# 519_jetson_nano_107.net
KiCad netlist of a schematic drawn in EAGLE
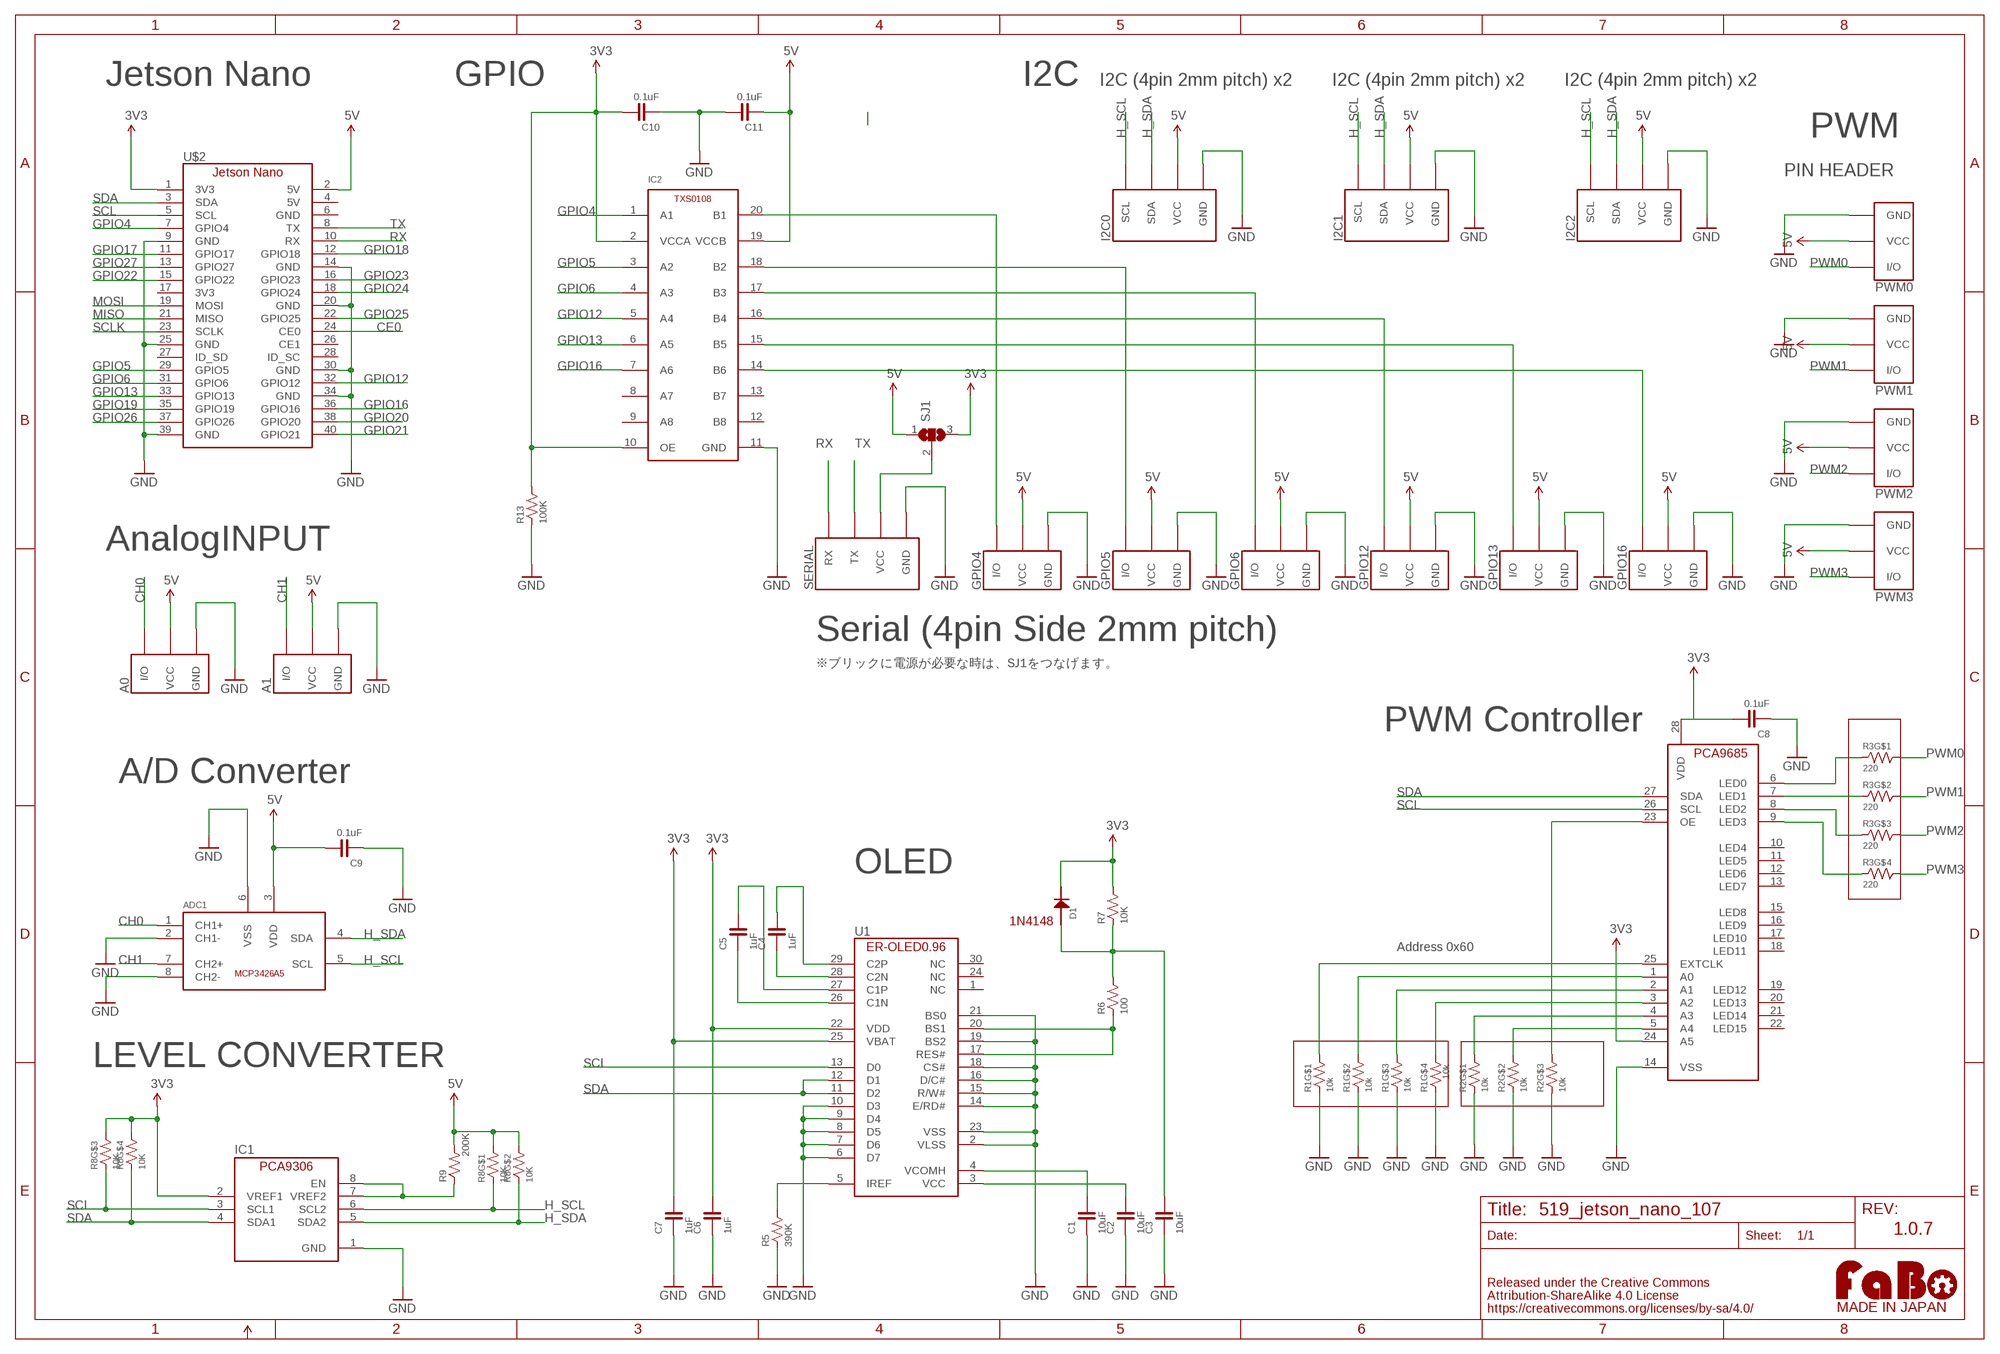
[diagram p0: schematic, sheet 1]

(export (version "E")
  (design (tool "Eeschema 10.0.6"))
  (components
    (comp (ref "A0")
      (value "FABO_BRICK_3PIN-S03B-PASK-2")
      (footprint "eagle-import:FABO_BRICK_3PIN_S03B-PASK-2")
      (libsource (lib "eagle-import") (part "FABO_BRICK_3PIN-S03B-PASK-2"))
    )
    (comp (ref "A1")
      (value "FABO_BRICK_3PIN-S03B-PASK-2")
      (footprint "eagle-import:FABO_BRICK_3PIN_S03B-PASK-2")
      (libsource (lib "eagle-import") (part "FABO_BRICK_3PIN-S03B-PASK-2"))
    )
    (comp (ref "ADC1")
      (value "MICROCHIP-MCP3426")
      (footprint "eagle-import:MICROCHIP-MCP3426")
      (libsource (lib "eagle-import") (part "MICROCHIP-MCP3426"))
    )
    (comp (ref "C1")
      (value "10uF")
      (footprint "eagle-import:0603-BOTTOM")
      (libsource (lib "eagle-import") (part "CAPACITOR-0603-BOTTOM"))
    )
    (comp (ref "C2")
      (value "10uF")
      (footprint "eagle-import:0603-BOTTOM")
      (libsource (lib "eagle-import") (part "CAPACITOR-0603-BOTTOM"))
    )
    (comp (ref "C3")
      (value "10uF")
      (footprint "eagle-import:0603-BOTTOM")
      (libsource (lib "eagle-import") (part "CAPACITOR-0603-BOTTOM"))
    )
    (comp (ref "C4")
      (value "1uF")
      (footprint "eagle-import:0603-BOTTOM")
      (libsource (lib "eagle-import") (part "CAPACITOR-0603-BOTTOM"))
    )
    (comp (ref "C5")
      (value "1uF")
      (footprint "eagle-import:0603-BOTTOM")
      (libsource (lib "eagle-import") (part "CAPACITOR-0603-BOTTOM"))
    )
    (comp (ref "C6")
      (value "1uF")
      (footprint "eagle-import:0603-BOTTOM")
      (libsource (lib "eagle-import") (part "CAPACITOR-0603-BOTTOM"))
    )
    (comp (ref "C7")
      (value "1uF")
      (footprint "eagle-import:0603-BOTTOM")
      (libsource (lib "eagle-import") (part "CAPACITOR-0603-BOTTOM"))
    )
    (comp (ref "C8")
      (value "0.1uF")
      (footprint "eagle-import:0603")
      (libsource (lib "eagle-import") (part "CAPACITOR-0603"))
    )
    (comp (ref "C9")
      (value "0.1uF")
      (footprint "eagle-import:0603")
      (libsource (lib "eagle-import") (part "CAPACITOR-0603"))
    )
    (comp (ref "C10")
      (value "0.1uF")
      (footprint "eagle-import:0603")
      (libsource (lib "eagle-import") (part "CAPACITOR-0603"))
    )
    (comp (ref "C11")
      (value "0.1uF")
      (footprint "eagle-import:0603")
      (libsource (lib "eagle-import") (part "CAPACITOR-0603"))
    )
    (comp (ref "D1")
      (value "1N4148")
      (footprint "eagle-import:1N4148W")
      (libsource (lib "eagle-import") (part "1N4148"))
    )
    (comp (ref "GPIO4")
      (value "FABO_BRICK_3PIN-B03B-PASK-1")
      (footprint "eagle-import:FABO_BRICK_3PIN_B03B-PASK-1")
      (libsource (lib "eagle-import") (part "FABO_BRICK_3PIN-B03B-PASK-1"))
    )
    (comp (ref "GPIO5")
      (value "FABO_BRICK_3PIN-B03B-PASK-1")
      (footprint "eagle-import:FABO_BRICK_3PIN_B03B-PASK-1")
      (libsource (lib "eagle-import") (part "FABO_BRICK_3PIN-B03B-PASK-1"))
    )
    (comp (ref "GPIO6")
      (value "FABO_BRICK_3PIN-B03B-PASK-1")
      (footprint "eagle-import:FABO_BRICK_3PIN_B03B-PASK-1")
      (libsource (lib "eagle-import") (part "FABO_BRICK_3PIN-B03B-PASK-1"))
    )
    (comp (ref "GPIO12")
      (value "FABO_BRICK_3PIN-B03B-PASK-1")
      (footprint "eagle-import:FABO_BRICK_3PIN_B03B-PASK-1")
      (libsource (lib "eagle-import") (part "FABO_BRICK_3PIN-B03B-PASK-1"))
    )
    (comp (ref "GPIO13")
      (value "FABO_BRICK_3PIN-B03B-PASK-1")
      (footprint "eagle-import:FABO_BRICK_3PIN_B03B-PASK-1")
      (libsource (lib "eagle-import") (part "FABO_BRICK_3PIN-B03B-PASK-1"))
    )
    (comp (ref "GPIO16")
      (value "FABO_BRICK_3PIN-B03B-PASK-1")
      (footprint "eagle-import:FABO_BRICK_3PIN_B03B-PASK-1")
      (libsource (lib "eagle-import") (part "FABO_BRICK_3PIN-B03B-PASK-1"))
    )
    (comp (ref "I2C0")
      (value "FABO_BRICK_I2C-S04B-PASK-2")
      (footprint "eagle-import:FABO_BRICK_I2C_S04B-PASK-2")
      (libsource (lib "eagle-import") (part "FABO_BRICK_I2C-S04B-PASK-2"))
    )
    (comp (ref "I2C1")
      (value "FABO_BRICK_I2C-B04B-PASK-1")
      (footprint "eagle-import:FABO_BRICK_I2C_B04B-PASK-1")
      (libsource (lib "eagle-import") (part "FABO_BRICK_I2C-B04B-PASK-1"))
    )
    (comp (ref "I2C2")
      (value "FABO_BRICK_I2C-B04B-PASK-1")
      (footprint "eagle-import:FABO_BRICK_I2C_B04B-PASK-1")
      (libsource (lib "eagle-import") (part "FABO_BRICK_I2C-B04B-PASK-1"))
    )
    (comp (ref "IC1")
      (value "PCA9306_SSOP")
      (footprint "eagle-import:8PIN-SSOP")
      (libsource (lib "eagle-import") (part "PCA9306_SSOP"))
    )
    (comp (ref "IC2")
      (value "TXS0108")
      (footprint "eagle-import:R-PUSON-N20")
      (libsource (lib "eagle-import") (part "TXS0108"))
    )
    (comp (ref "PWM0")
      (value "FABO_BRICK_3PIN-HEADER")
      (footprint "eagle-import:FABO_BRICK_3PIN_HEADER")
      (libsource (lib "eagle-import") (part "FABO_BRICK_3PIN-HEADER"))
    )
    (comp (ref "PWM1")
      (value "FABO_BRICK_3PIN-HEADER")
      (footprint "eagle-import:FABO_BRICK_3PIN_HEADER")
      (libsource (lib "eagle-import") (part "FABO_BRICK_3PIN-HEADER"))
    )
    (comp (ref "PWM2")
      (value "FABO_BRICK_3PIN-HEADER")
      (footprint "eagle-import:FABO_BRICK_3PIN_HEADER")
      (libsource (lib "eagle-import") (part "FABO_BRICK_3PIN-HEADER"))
    )
    (comp (ref "PWM3")
      (value "FABO_BRICK_3PIN-HEADER")
      (footprint "eagle-import:FABO_BRICK_3PIN_HEADER")
      (libsource (lib "eagle-import") (part "FABO_BRICK_3PIN-HEADER"))
    )
    (comp (ref "R1")
      (value "10k")
      (footprint "eagle-import:EXBV8V")
      (libsource (lib "eagle-import") (part "RESISTOR_ARRAY"))
    )
    (comp (ref "R2")
      (value "10k")
      (footprint "eagle-import:EXBV8V")
      (libsource (lib "eagle-import") (part "RESISTOR_ARRAY"))
    )
    (comp (ref "R3")
      (value "220")
      (footprint "eagle-import:EXBV8V")
      (libsource (lib "eagle-import") (part "RESISTOR_ARRAY"))
    )
    (comp (ref "R5")
      (value "390K")
      (footprint "eagle-import:0603-BOTTOM")
      (libsource (lib "eagle-import") (part "RESISTOR-0603-BOTTOM"))
    )
    (comp (ref "R6")
      (value "100")
      (footprint "eagle-import:0603-BOTTOM")
      (libsource (lib "eagle-import") (part "RESISTOR-0603-BOTTOM"))
    )
    (comp (ref "R7")
      (value "10K")
      (footprint "eagle-import:0603-BOTTOM")
      (libsource (lib "eagle-import") (part "RESISTOR-0603-BOTTOM"))
    )
    (comp (ref "R8")
      (value "10K")
      (footprint "eagle-import:EXBV8V")
      (libsource (lib "eagle-import") (part "RESISTOR_ARRAY"))
    )
    (comp (ref "R9")
      (value "200K")
      (footprint "eagle-import:0603")
      (libsource (lib "eagle-import") (part "RESISTOR-0603"))
    )
    (comp (ref "R13")
      (value "100K")
      (footprint "eagle-import:0603-BOTTOM")
      (libsource (lib "eagle-import") (part "RESISTOR-0603-BOTTOM"))
    )
    (comp (ref "SERIAL")
      (value "FABO_BRICK_SERIAL-B04B-PASK-1")
      (footprint "eagle-import:FABO_BRICK_SERIAL_B04B-PASK-1")
      (libsource (lib "eagle-import") (part "FABO_BRICK_SERIAL-B04B-PASK-1"))
    )
    (comp (ref "SJ1")
      (value "SJ2W")
      (footprint "eagle-import:SJ_2")
      (libsource (lib "eagle-import") (part "SJ2W"))
    )
    (comp (ref "U$2")
      (value "JETSON_NANO_WIDE")
      (footprint "eagle-import:JETSON_NANO_WIDE")
      (libsource (lib "eagle-import") (part "JETSON_NANO_WIDE"))
    )
    (comp (ref "U$9")
      (value "PCA9685")
      (footprint "eagle-import:PCA9685")
      (libsource (lib "eagle-import") (part "PCA9685"))
    )
    (comp (ref "U$14")
      (value "LOGO_FABO-M")
      (footprint "eagle-import:LOGO_FABO_MS")
      (libsource (lib "eagle-import") (part "LOGO_FABO-M"))
    )
    (comp (ref "U1")
      (value "ER-OLED0.96-1ER-CON30HT-1")
      (footprint "eagle-import:ER-CON30HT-1")
      (libsource (lib "eagle-import") (part "ER-OLED0.96-1ER-CON30HT-1"))
    )
  )
  (nets
    (net (code "1") (name "/CE0") (class "Default")
      (node (ref "U$2") (pin "24") (pinfunction "CE0_24") (pintype "bidirectional"))
    )
    (net (code "2") (name "/CH0") (class "Default")
      (node (ref "A0") (pin "I/O") (pinfunction "I/O_I/O") (pintype "bidirectional"))
      (node (ref "ADC1") (pin "1") (pinfunction "CH1+_1") (pintype "bidirectional"))
    )
    (net (code "3") (name "/CH1") (class "Default")
      (node (ref "A1") (pin "I/O") (pinfunction "I/O_I/O") (pintype "bidirectional"))
      (node (ref "ADC1") (pin "7") (pinfunction "CH2+_7") (pintype "bidirectional"))
    )
    (net (code "4") (name "/GPIO4") (class "Default")
      (node (ref "IC2") (pin "1") (pinfunction "A1_1") (pintype "bidirectional"))
      (node (ref "U$2") (pin "7") (pinfunction "GPIO4_7") (pintype "bidirectional"))
    )
    (net (code "5") (name "/GPIO5") (class "Default")
      (node (ref "IC2") (pin "3") (pinfunction "A2_3") (pintype "bidirectional"))
      (node (ref "U$2") (pin "29") (pinfunction "GPIO5_29") (pintype "bidirectional"))
    )
    (net (code "6") (name "/GPIO6") (class "Default")
      (node (ref "IC2") (pin "4") (pinfunction "A3_4") (pintype "bidirectional"))
      (node (ref "U$2") (pin "31") (pinfunction "GPIO6_31") (pintype "bidirectional"))
    )
    (net (code "7") (name "/GPIO12") (class "Default")
      (node (ref "IC2") (pin "5") (pinfunction "A4_5") (pintype "bidirectional"))
      (node (ref "U$2") (pin "32") (pinfunction "GPIO12_32") (pintype "bidirectional"))
    )
    (net (code "8") (name "/GPIO13") (class "Default")
      (node (ref "IC2") (pin "6") (pinfunction "A5_6") (pintype "bidirectional"))
      (node (ref "U$2") (pin "33") (pinfunction "GPIO13_33") (pintype "bidirectional"))
    )
    (net (code "9") (name "/GPIO16") (class "Default")
      (node (ref "IC2") (pin "7") (pinfunction "A6_7") (pintype "bidirectional"))
      (node (ref "U$2") (pin "36") (pinfunction "GPIO16_36") (pintype "bidirectional"))
    )
    (net (code "10") (name "/GPIO17") (class "Default")
      (node (ref "U$2") (pin "11") (pinfunction "GPIO17_11") (pintype "bidirectional"))
    )
    (net (code "11") (name "/GPIO18") (class "Default")
      (node (ref "U$2") (pin "12") (pinfunction "GPIO18_12") (pintype "bidirectional"))
    )
    (net (code "12") (name "/GPIO19") (class "Default")
      (node (ref "U$2") (pin "35") (pinfunction "GPIO19_35") (pintype "bidirectional"))
    )
    (net (code "13") (name "/GPIO20") (class "Default")
      (node (ref "U$2") (pin "38") (pinfunction "GPIO20_38") (pintype "bidirectional"))
    )
    (net (code "14") (name "/GPIO21") (class "Default")
      (node (ref "U$2") (pin "40") (pinfunction "GPIO21_40") (pintype "bidirectional"))
    )
    (net (code "15") (name "/GPIO22") (class "Default")
      (node (ref "U$2") (pin "15") (pinfunction "GPIO22_15") (pintype "bidirectional"))
    )
    (net (code "16") (name "/GPIO23") (class "Default")
      (node (ref "U$2") (pin "16") (pinfunction "GPIO23_16") (pintype "bidirectional"))
    )
    (net (code "17") (name "/GPIO24") (class "Default")
      (node (ref "U$2") (pin "18") (pinfunction "GPIO24_18") (pintype "bidirectional"))
    )
    (net (code "18") (name "/GPIO25") (class "Default")
      (node (ref "U$2") (pin "22") (pinfunction "GPIO25_22") (pintype "bidirectional"))
    )
    (net (code "19") (name "/GPIO26") (class "Default")
      (node (ref "U$2") (pin "37") (pinfunction "GPIO26_37") (pintype "bidirectional"))
    )
    (net (code "20") (name "/GPIO27") (class "Default")
      (node (ref "U$2") (pin "13") (pinfunction "GPIO27_13") (pintype "bidirectional"))
    )
    (net (code "21") (name "/H_SCL") (class "Default")
      (node (ref "ADC1") (pin "5") (pinfunction "SCL_5") (pintype "bidirectional"))
      (node (ref "I2C0") (pin "SCL") (pinfunction "SCL_SCL") (pintype "bidirectional"))
      (node (ref "I2C1") (pin "SCL") (pinfunction "SCL_SCL") (pintype "bidirectional"))
      (node (ref "I2C2") (pin "SCL") (pinfunction "SCL_SCL") (pintype "bidirectional"))
      (node (ref "IC1") (pin "6") (pinfunction "SCL2_6") (pintype "bidirectional"))
      (node (ref "R8") (pin "1") (pinfunction "1_1") (pintype "bidirectional"))
    )
    (net (code "22") (name "/H_SDA") (class "Default")
      (node (ref "ADC1") (pin "4") (pinfunction "SDA_4") (pintype "bidirectional"))
      (node (ref "I2C0") (pin "SDA") (pinfunction "SDA_SDA") (pintype "bidirectional"))
      (node (ref "I2C1") (pin "SDA") (pinfunction "SDA_SDA") (pintype "bidirectional"))
      (node (ref "I2C2") (pin "SDA") (pinfunction "SDA_SDA") (pintype "bidirectional"))
      (node (ref "IC1") (pin "5") (pinfunction "SDA2_5") (pintype "bidirectional"))
      (node (ref "R8") (pin "2") (pinfunction "1_2") (pintype "bidirectional"))
    )
    (net (code "23") (name "/MISO") (class "Default")
      (node (ref "U$2") (pin "21") (pinfunction "MISO_21") (pintype "bidirectional"))
    )
    (net (code "24") (name "/MOSI") (class "Default")
      (node (ref "U$2") (pin "19") (pinfunction "MOSI_19") (pintype "bidirectional"))
    )
    (net (code "25") (name "/PWM0") (class "Default")
      (node (ref "PWM0") (pin "I/O") (pinfunction "I/O_I/O") (pintype "bidirectional"))
      (node (ref "R3") (pin "8") (pinfunction "2_8") (pintype "bidirectional"))
    )
    (net (code "26") (name "/PWM1") (class "Default")
      (node (ref "PWM1") (pin "I/O") (pinfunction "I/O_I/O") (pintype "bidirectional"))
      (node (ref "R3") (pin "7") (pinfunction "2_7") (pintype "bidirectional"))
    )
    (net (code "27") (name "/PWM2") (class "Default")
      (node (ref "PWM2") (pin "I/O") (pinfunction "I/O_I/O") (pintype "bidirectional"))
      (node (ref "R3") (pin "6") (pinfunction "2_6") (pintype "bidirectional"))
    )
    (net (code "28") (name "/PWM3") (class "Default")
      (node (ref "PWM3") (pin "I/O") (pinfunction "I/O_I/O") (pintype "bidirectional"))
      (node (ref "R3") (pin "5") (pinfunction "2_5") (pintype "bidirectional"))
    )
    (net (code "29") (name "/RX") (class "Default")
      (node (ref "SERIAL") (pin "RX") (pinfunction "RX_RX") (pintype "bidirectional"))
      (node (ref "U$2") (pin "10") (pinfunction "RX_10") (pintype "bidirectional"))
    )
    (net (code "30") (name "/SCL") (class "Default")
      (node (ref "IC1") (pin "3") (pinfunction "SCL1_3") (pintype "bidirectional"))
      (node (ref "R8") (pin "3") (pinfunction "1_3") (pintype "bidirectional"))
      (node (ref "U$2") (pin "5") (pinfunction "SCL_5") (pintype "bidirectional"))
      (node (ref "U$9") (pin "26") (pinfunction "SCL_26") (pintype "bidirectional"))
      (node (ref "U1") (pin "13") (pinfunction "D0_13") (pintype "bidirectional"))
    )
    (net (code "31") (name "/SCLK") (class "Default")
      (node (ref "U$2") (pin "23") (pinfunction "SCLK_23") (pintype "bidirectional"))
    )
    (net (code "32") (name "/SDA") (class "Default")
      (node (ref "IC1") (pin "4") (pinfunction "SDA1_4") (pintype "bidirectional"))
      (node (ref "R8") (pin "4") (pinfunction "1_4") (pintype "bidirectional"))
      (node (ref "U$2") (pin "3") (pinfunction "SDA_3") (pintype "bidirectional"))
      (node (ref "U$9") (pin "27") (pinfunction "SDA_27") (pintype "bidirectional"))
      (node (ref "U1") (pin "11") (pinfunction "D2_11") (pintype "bidirectional"))
      (node (ref "U1") (pin "12") (pinfunction "D1_12") (pintype "bidirectional"))
    )
    (net (code "33") (name "/TX") (class "Default")
      (node (ref "SERIAL") (pin "TX") (pinfunction "TX_TX") (pintype "bidirectional"))
      (node (ref "U$2") (pin "8") (pinfunction "TX_8") (pintype "bidirectional"))
    )
    (net (code "34") (name "3V3") (class "Default")
      (node (ref "C10") (pin "2") (pinfunction "2_2") (pintype "passive"))
      (node (ref "C6") (pin "2") (pinfunction "2_2") (pintype "passive"))
      (node (ref "C7") (pin "2") (pinfunction "2_2") (pintype "passive"))
      (node (ref "C8") (pin "2") (pinfunction "2_2") (pintype "passive"))
      (node (ref "D1") (pin "CATHODE") (pinfunction "CATHODE_CATHODE") (pintype "bidirectional"))
      (node (ref "IC1") (pin "2") (pinfunction "VREF1_2") (pintype "bidirectional"))
      (node (ref "IC2") (pin "10") (pinfunction "OE_10") (pintype "bidirectional"))
      (node (ref "IC2") (pin "2") (pinfunction "VCCA_2") (pintype "bidirectional"))
      (node (ref "R13") (pin "2") (pinfunction "2_2") (pintype "bidirectional"))
      (node (ref "R7") (pin "2") (pinfunction "2_2") (pintype "bidirectional"))
      (node (ref "R8") (pin "5") (pinfunction "2_5") (pintype "bidirectional"))
      (node (ref "R8") (pin "6") (pinfunction "2_6") (pintype "bidirectional"))
      (node (ref "SJ1") (pin "3") (pinfunction "3_3") (pintype "passive"))
      (node (ref "U$2") (pin "1") (pinfunction "3V3_1") (pintype "bidirectional"))
      (node (ref "U$9") (pin "24") (pinfunction "A5_24") (pintype "bidirectional"))
      (node (ref "U$9") (pin "28") (pinfunction "VDD_28") (pintype "bidirectional"))
      (node (ref "U1") (pin "22") (pinfunction "VDD_22") (pintype "bidirectional"))
      (node (ref "U1") (pin "25") (pinfunction "VBAT_25") (pintype "bidirectional"))
    )
    (net (code "35") (name "5V") (class "Default")
      (node (ref "A0") (pin "VCC") (pinfunction "VCC_VCC") (pintype "bidirectional"))
      (node (ref "A1") (pin "VCC") (pinfunction "VCC_VCC") (pintype "bidirectional"))
      (node (ref "ADC1") (pin "3") (pinfunction "VDD_3") (pintype "bidirectional"))
      (node (ref "C11") (pin "1") (pinfunction "1_1") (pintype "passive"))
      (node (ref "C9") (pin "2") (pinfunction "2_2") (pintype "passive"))
      (node (ref "GPIO12") (pin "VCC") (pinfunction "VCC_VCC") (pintype "bidirectional"))
      (node (ref "GPIO13") (pin "VCC") (pinfunction "VCC_VCC") (pintype "bidirectional"))
      (node (ref "GPIO16") (pin "VCC") (pinfunction "VCC_VCC") (pintype "bidirectional"))
      (node (ref "GPIO4") (pin "VCC") (pinfunction "VCC_VCC") (pintype "bidirectional"))
      (node (ref "GPIO5") (pin "VCC") (pinfunction "VCC_VCC") (pintype "bidirectional"))
      (node (ref "GPIO6") (pin "VCC") (pinfunction "VCC_VCC") (pintype "bidirectional"))
      (node (ref "I2C0") (pin "VCC") (pinfunction "VCC_VCC") (pintype "bidirectional"))
      (node (ref "I2C1") (pin "VCC") (pinfunction "VCC_VCC") (pintype "bidirectional"))
      (node (ref "I2C2") (pin "VCC") (pinfunction "VCC_VCC") (pintype "bidirectional"))
      (node (ref "IC2") (pin "19") (pinfunction "VCCB_19") (pintype "bidirectional"))
      (node (ref "PWM0") (pin "VCC") (pinfunction "VCC_VCC") (pintype "bidirectional"))
      (node (ref "PWM1") (pin "VCC") (pinfunction "VCC_VCC") (pintype "bidirectional"))
      (node (ref "PWM2") (pin "VCC") (pinfunction "VCC_VCC") (pintype "bidirectional"))
      (node (ref "PWM3") (pin "VCC") (pinfunction "VCC_VCC") (pintype "bidirectional"))
      (node (ref "R8") (pin "7") (pinfunction "2_7") (pintype "bidirectional"))
      (node (ref "R8") (pin "8") (pinfunction "2_8") (pintype "bidirectional"))
      (node (ref "R9") (pin "2") (pinfunction "2_2") (pintype "bidirectional"))
      (node (ref "SJ1") (pin "1") (pinfunction "1_1") (pintype "passive"))
      (node (ref "U$2") (pin "2") (pinfunction "5V_2") (pintype "bidirectional"))
    )
    (net (code "36") (name "GND") (class "Default")
      (node (ref "A0") (pin "GND") (pinfunction "GND_GND") (pintype "bidirectional"))
      (node (ref "A1") (pin "GND") (pinfunction "GND_GND") (pintype "bidirectional"))
      (node (ref "ADC1") (pin "2") (pinfunction "CH1-_2") (pintype "bidirectional"))
      (node (ref "ADC1") (pin "6") (pinfunction "VSS_6") (pintype "bidirectional"))
      (node (ref "ADC1") (pin "8") (pinfunction "CH2-_8") (pintype "bidirectional"))
      (node (ref "C1") (pin "1") (pinfunction "1_1") (pintype "passive"))
      (node (ref "C10") (pin "1") (pinfunction "1_1") (pintype "passive"))
      (node (ref "C11") (pin "2") (pinfunction "2_2") (pintype "passive"))
      (node (ref "C2") (pin "1") (pinfunction "1_1") (pintype "passive"))
      (node (ref "C3") (pin "1") (pinfunction "1_1") (pintype "passive"))
      (node (ref "C6") (pin "1") (pinfunction "1_1") (pintype "passive"))
      (node (ref "C7") (pin "1") (pinfunction "1_1") (pintype "passive"))
      (node (ref "C8") (pin "1") (pinfunction "1_1") (pintype "passive"))
      (node (ref "C9") (pin "1") (pinfunction "1_1") (pintype "passive"))
      (node (ref "GPIO12") (pin "GND") (pinfunction "GND_GND") (pintype "bidirectional"))
      (node (ref "GPIO13") (pin "GND") (pinfunction "GND_GND") (pintype "bidirectional"))
      (node (ref "GPIO16") (pin "GND") (pinfunction "GND_GND") (pintype "bidirectional"))
      (node (ref "GPIO4") (pin "GND") (pinfunction "GND_GND") (pintype "bidirectional"))
      (node (ref "GPIO5") (pin "GND") (pinfunction "GND_GND") (pintype "bidirectional"))
      (node (ref "GPIO6") (pin "GND") (pinfunction "GND_GND") (pintype "bidirectional"))
      (node (ref "I2C0") (pin "GND") (pinfunction "GND_GND") (pintype "bidirectional"))
      (node (ref "I2C1") (pin "GND") (pinfunction "GND_GND") (pintype "bidirectional"))
      (node (ref "I2C2") (pin "GND") (pinfunction "GND_GND") (pintype "bidirectional"))
      (node (ref "IC1") (pin "1") (pinfunction "GND_1") (pintype "bidirectional"))
      (node (ref "IC2") (pin "11") (pinfunction "GND_11") (pintype "bidirectional"))
      (node (ref "PWM0") (pin "GND") (pinfunction "GND_GND") (pintype "bidirectional"))
      (node (ref "PWM1") (pin "GND") (pinfunction "GND_GND") (pintype "bidirectional"))
      (node (ref "PWM2") (pin "GND") (pinfunction "GND_GND") (pintype "bidirectional"))
      (node (ref "PWM3") (pin "GND") (pinfunction "GND_GND") (pintype "bidirectional"))
      (node (ref "R1") (pin "1") (pinfunction "1_1") (pintype "bidirectional"))
      (node (ref "R1") (pin "2") (pinfunction "1_2") (pintype "bidirectional"))
      (node (ref "R1") (pin "3") (pinfunction "1_3") (pintype "bidirectional"))
      (node (ref "R1") (pin "4") (pinfunction "1_4") (pintype "bidirectional"))
      (node (ref "R13") (pin "1") (pinfunction "1_1") (pintype "bidirectional"))
      (node (ref "R2") (pin "1") (pinfunction "1_1") (pintype "bidirectional"))
      (node (ref "R2") (pin "2") (pinfunction "1_2") (pintype "bidirectional"))
      (node (ref "R2") (pin "3") (pinfunction "1_3") (pintype "bidirectional"))
      (node (ref "R5") (pin "1") (pinfunction "1_1") (pintype "bidirectional"))
      (node (ref "SERIAL") (pin "GND") (pinfunction "GND_GND") (pintype "bidirectional"))
      (node (ref "U$2") (pin "14") (pinfunction "GND_14") (pintype "bidirectional"))
      (node (ref "U$2") (pin "20") (pinfunction "GND_20") (pintype "bidirectional"))
      (node (ref "U$2") (pin "25") (pinfunction "GND_25") (pintype "bidirectional"))
      (node (ref "U$2") (pin "30") (pinfunction "GND_30") (pintype "bidirectional"))
      (node (ref "U$2") (pin "34") (pinfunction "GND_34") (pintype "bidirectional"))
      (node (ref "U$2") (pin "39") (pinfunction "GND_39") (pintype "bidirectional"))
      (node (ref "U$2") (pin "9") (pinfunction "GND_9") (pintype "bidirectional"))
      (node (ref "U$9") (pin "14") (pinfunction "VSS_14") (pintype "bidirectional"))
      (node (ref "U1") (pin "10") (pinfunction "D3_10") (pintype "bidirectional"))
      (node (ref "U1") (pin "14") (pinfunction "E/RD#_14") (pintype "bidirectional"))
      (node (ref "U1") (pin "15") (pinfunction "R/W#_15") (pintype "bidirectional"))
      (node (ref "U1") (pin "16") (pinfunction "D/C#_16") (pintype "bidirectional"))
      (node (ref "U1") (pin "18") (pinfunction "CS#_18") (pintype "bidirectional"))
      (node (ref "U1") (pin "19") (pinfunction "BS2_19") (pintype "bidirectional"))
      (node (ref "U1") (pin "2") (pinfunction "VLSS_2") (pintype "bidirectional"))
      (node (ref "U1") (pin "21") (pinfunction "BS0_21") (pintype "bidirectional"))
      (node (ref "U1") (pin "23") (pinfunction "VSS_23") (pintype "bidirectional"))
      (node (ref "U1") (pin "6") (pinfunction "D7_6") (pintype "bidirectional"))
      (node (ref "U1") (pin "7") (pinfunction "D6_7") (pintype "bidirectional"))
      (node (ref "U1") (pin "8") (pinfunction "D5_8") (pintype "bidirectional"))
      (node (ref "U1") (pin "9") (pinfunction "D4_9") (pintype "bidirectional"))
    )
    (net (code "37") (name "Net-(C3-Pad2)") (class "Default")
      (node (ref "C3") (pin "2") (pinfunction "2_2") (pintype "passive"))
      (node (ref "D1") (pin "ANODE") (pinfunction "ANODE_ANODE") (pintype "bidirectional"))
      (node (ref "R6") (pin "2") (pinfunction "2_2") (pintype "bidirectional"))
      (node (ref "R7") (pin "1") (pinfunction "1_1") (pintype "bidirectional"))
    )
    (net (code "38") (name "Net-(IC1-EN)") (class "Default")
      (node (ref "IC1") (pin "7") (pinfunction "VREF2_7") (pintype "bidirectional"))
      (node (ref "IC1") (pin "8") (pinfunction "EN_8") (pintype "bidirectional"))
      (node (ref "R9") (pin "1") (pinfunction "1_1") (pintype "bidirectional"))
    )
    (net (code "39") (name "Net-(IC2-B1)") (class "Default")
      (node (ref "GPIO4") (pin "I/O") (pinfunction "I/O_I/O") (pintype "bidirectional"))
      (node (ref "IC2") (pin "20") (pinfunction "B1_20") (pintype "bidirectional"))
    )
    (net (code "40") (name "Net-(IC2-B2)") (class "Default")
      (node (ref "GPIO5") (pin "I/O") (pinfunction "I/O_I/O") (pintype "bidirectional"))
      (node (ref "IC2") (pin "18") (pinfunction "B2_18") (pintype "bidirectional"))
    )
    (net (code "41") (name "Net-(IC2-B3)") (class "Default")
      (node (ref "GPIO6") (pin "I/O") (pinfunction "I/O_I/O") (pintype "bidirectional"))
      (node (ref "IC2") (pin "17") (pinfunction "B3_17") (pintype "bidirectional"))
    )
    (net (code "42") (name "Net-(IC2-B4)") (class "Default")
      (node (ref "GPIO12") (pin "I/O") (pinfunction "I/O_I/O") (pintype "bidirectional"))
      (node (ref "IC2") (pin "16") (pinfunction "B4_16") (pintype "bidirectional"))
    )
    (net (code "43") (name "Net-(IC2-B5)") (class "Default")
      (node (ref "GPIO13") (pin "I/O") (pinfunction "I/O_I/O") (pintype "bidirectional"))
      (node (ref "IC2") (pin "15") (pinfunction "B5_15") (pintype "bidirectional"))
    )
    (net (code "44") (name "Net-(IC2-B6)") (class "Default")
      (node (ref "GPIO16") (pin "I/O") (pinfunction "I/O_I/O") (pintype "bidirectional"))
      (node (ref "IC2") (pin "14") (pinfunction "B6_14") (pintype "bidirectional"))
    )
    (net (code "45") (name "Net-(R1A-2)") (class "Default")
      (node (ref "R1") (pin "8") (pinfunction "2_8") (pintype "bidirectional"))
      (node (ref "U$9") (pin "25") (pinfunction "EXTCLK_25") (pintype "bidirectional"))
    )
    (net (code "46") (name "Net-(R1B-2)") (class "Default")
      (node (ref "R1") (pin "7") (pinfunction "2_7") (pintype "bidirectional"))
      (node (ref "U$9") (pin "1") (pinfunction "A0_1") (pintype "bidirectional"))
    )
    (net (code "47") (name "Net-(R1C-2)") (class "Default")
      (node (ref "R1") (pin "6") (pinfunction "2_6") (pintype "bidirectional"))
      (node (ref "U$9") (pin "2") (pinfunction "A1_2") (pintype "bidirectional"))
    )
    (net (code "48") (name "Net-(R1D-2)") (class "Default")
      (node (ref "R1") (pin "5") (pinfunction "2_5") (pintype "bidirectional"))
      (node (ref "U$9") (pin "3") (pinfunction "A2_3") (pintype "bidirectional"))
    )
    (net (code "49") (name "Net-(R2A-2)") (class "Default")
      (node (ref "R2") (pin "8") (pinfunction "2_8") (pintype "bidirectional"))
      (node (ref "U$9") (pin "4") (pinfunction "A3_4") (pintype "bidirectional"))
    )
    (net (code "50") (name "Net-(R2B-2)") (class "Default")
      (node (ref "R2") (pin "7") (pinfunction "2_7") (pintype "bidirectional"))
      (node (ref "U$9") (pin "5") (pinfunction "A4_5") (pintype "bidirectional"))
    )
    (net (code "51") (name "Net-(R2C-2)") (class "Default")
      (node (ref "R2") (pin "6") (pinfunction "2_6") (pintype "bidirectional"))
      (node (ref "U$9") (pin "23") (pinfunction "OE_23") (pintype "bidirectional"))
    )
    (net (code "52") (name "Net-(R3B-1)") (class "Default")
      (node (ref "R3") (pin "2") (pinfunction "1_2") (pintype "bidirectional"))
      (node (ref "U$9") (pin "7") (pinfunction "LED1_7") (pintype "bidirectional"))
    )
    (net (code "53") (name "Net-(R3C-1)") (class "Default")
      (node (ref "R3") (pin "3") (pinfunction "1_3") (pintype "bidirectional"))
      (node (ref "U$9") (pin "8") (pinfunction "LED2_8") (pintype "bidirectional"))
    )
    (net (code "54") (name "Net-(R3D-1)") (class "Default")
      (node (ref "R3") (pin "4") (pinfunction "1_4") (pintype "bidirectional"))
      (node (ref "U$9") (pin "9") (pinfunction "LED3_9") (pintype "bidirectional"))
    )
    (net (code "55") (name "Net-(SERIAL-PadVCC)") (class "Default")
      (node (ref "SERIAL") (pin "VCC") (pinfunction "VCC_VCC") (pintype "bidirectional"))
      (node (ref "SJ1") (pin "2") (pinfunction "2_2") (pintype "passive"))
    )
    (net (code "56") (name "Net-(U$9-LED0)") (class "Default")
      (node (ref "R3") (pin "1") (pinfunction "1_1") (pintype "bidirectional"))
      (node (ref "U$9") (pin "6") (pinfunction "LED0_6") (pintype "bidirectional"))
    )
    (net (code "57") (name "Net-(U1-BS1)") (class "Default")
      (node (ref "R6") (pin "1") (pinfunction "1_1") (pintype "bidirectional"))
      (node (ref "U1") (pin "17") (pinfunction "RES#_17") (pintype "bidirectional"))
      (node (ref "U1") (pin "20") (pinfunction "BS1_20") (pintype "bidirectional"))
    )
    (net (code "58") (name "Net-(U1-C1N)") (class "Default")
      (node (ref "C5") (pin "1") (pinfunction "1_1") (pintype "passive"))
      (node (ref "U1") (pin "26") (pinfunction "C1N_26") (pintype "bidirectional"))
    )
    (net (code "59") (name "Net-(U1-C1P)") (class "Default")
      (node (ref "C5") (pin "2") (pinfunction "2_2") (pintype "passive"))
      (node (ref "U1") (pin "27") (pinfunction "C1P_27") (pintype "bidirectional"))
    )
    (net (code "60") (name "Net-(U1-C2N)") (class "Default")
      (node (ref "C4") (pin "1") (pinfunction "1_1") (pintype "passive"))
      (node (ref "U1") (pin "28") (pinfunction "C2N_28") (pintype "bidirectional"))
    )
    (net (code "61") (name "Net-(U1-C2P)") (class "Default")
      (node (ref "C4") (pin "2") (pinfunction "2_2") (pintype "passive"))
      (node (ref "U1") (pin "29") (pinfunction "C2P_29") (pintype "bidirectional"))
    )
    (net (code "62") (name "Net-(U1-IREF)") (class "Default")
      (node (ref "R5") (pin "2") (pinfunction "2_2") (pintype "bidirectional"))
      (node (ref "U1") (pin "5") (pinfunction "IREF_5") (pintype "bidirectional"))
    )
    (net (code "63") (name "Net-(U1-VCC)") (class "Default")
      (node (ref "C2") (pin "2") (pinfunction "2_2") (pintype "passive"))
      (node (ref "U1") (pin "3") (pinfunction "VCC_3") (pintype "bidirectional"))
    )
    (net (code "64") (name "Net-(U1-VCOMH)") (class "Default")
      (node (ref "C1") (pin "2") (pinfunction "2_2") (pintype "passive"))
      (node (ref "U1") (pin "4") (pinfunction "VCOMH_4") (pintype "bidirectional"))
    )
    (net (code "65") (name "unconnected-(IC2-A7-Pad8)") (class "Default")
      (node (ref "IC2") (pin "8") (pinfunction "A7_8") (pintype "bidirectional"))
    )
    (net (code "66") (name "unconnected-(IC2-A8-Pad9)") (class "Default")
      (node (ref "IC2") (pin "9") (pinfunction "A8_9") (pintype "bidirectional"))
    )
    (net (code "67") (name "unconnected-(IC2-B7-Pad13)") (class "Default")
      (node (ref "IC2") (pin "13") (pinfunction "B7_13") (pintype "bidirectional"))
    )
    (net (code "68") (name "unconnected-(IC2-B8-Pad12)") (class "Default")
      (node (ref "IC2") (pin "12") (pinfunction "B8_12") (pintype "bidirectional"))
    )
    (net (code "69") (name "unconnected-(U$2-3V3-Pad17)") (class "Default")
      (node (ref "U$2") (pin "17") (pinfunction "3V3_17") (pintype "bidirectional"))
    )
    (net (code "70") (name "unconnected-(U$2-5V-Pad4)") (class "Default")
      (node (ref "U$2") (pin "4") (pinfunction "5V_4") (pintype "bidirectional"))
    )
    (net (code "71") (name "unconnected-(U$2-CE1-Pad26)") (class "Default")
      (node (ref "U$2") (pin "26") (pinfunction "CE1_26") (pintype "bidirectional"))
    )
    (net (code "72") (name "unconnected-(U$2-GND-Pad6)") (class "Default")
      (node (ref "U$2") (pin "6") (pinfunction "GND_6") (pintype "bidirectional"))
    )
    (net (code "73") (name "unconnected-(U$2-ID_SC-Pad28)") (class "Default")
      (node (ref "U$2") (pin "28") (pinfunction "ID_SC_28") (pintype "bidirectional"))
    )
    (net (code "74") (name "unconnected-(U$2-ID_SD-Pad27)") (class "Default")
      (node (ref "U$2") (pin "27") (pinfunction "ID_SD_27") (pintype "bidirectional"))
    )
    (net (code "75") (name "unconnected-(U$9-LED4-Pad10)") (class "Default")
      (node (ref "U$9") (pin "10") (pinfunction "LED4_10") (pintype "bidirectional"))
    )
    (net (code "76") (name "unconnected-(U$9-LED5-Pad11)") (class "Default")
      (node (ref "U$9") (pin "11") (pinfunction "LED5_11") (pintype "bidirectional"))
    )
    (net (code "77") (name "unconnected-(U$9-LED6-Pad12)") (class "Default")
      (node (ref "U$9") (pin "12") (pinfunction "LED6_12") (pintype "bidirectional"))
    )
    (net (code "78") (name "unconnected-(U$9-LED7-Pad13)") (class "Default")
      (node (ref "U$9") (pin "13") (pinfunction "LED7_13") (pintype "bidirectional"))
    )
    (net (code "79") (name "unconnected-(U$9-LED8-Pad15)") (class "Default")
      (node (ref "U$9") (pin "15") (pinfunction "LED8_15") (pintype "bidirectional"))
    )
    (net (code "80") (name "unconnected-(U$9-LED9-Pad16)") (class "Default")
      (node (ref "U$9") (pin "16") (pinfunction "LED9_16") (pintype "bidirectional"))
    )
    (net (code "81") (name "unconnected-(U$9-LED10-Pad17)") (class "Default")
      (node (ref "U$9") (pin "17") (pinfunction "LED10_17") (pintype "bidirectional"))
    )
    (net (code "82") (name "unconnected-(U$9-LED11-Pad18)") (class "Default")
      (node (ref "U$9") (pin "18") (pinfunction "LED11_18") (pintype "bidirectional"))
    )
    (net (code "83") (name "unconnected-(U$9-LED12-Pad19)") (class "Default")
      (node (ref "U$9") (pin "19") (pinfunction "LED12_19") (pintype "bidirectional"))
    )
    (net (code "84") (name "unconnected-(U$9-LED13-Pad20)") (class "Default")
      (node (ref "U$9") (pin "20") (pinfunction "LED13_20") (pintype "bidirectional"))
    )
    (net (code "85") (name "unconnected-(U$9-LED14-Pad21)") (class "Default")
      (node (ref "U$9") (pin "21") (pinfunction "LED14_21") (pintype "bidirectional"))
    )
    (net (code "86") (name "unconnected-(U$9-LED15-Pad22)") (class "Default")
      (node (ref "U$9") (pin "22") (pinfunction "LED15_22") (pintype "bidirectional"))
    )
    (net (code "87") (name "unconnected-(U1-NC-Pad1)") (class "Default")
      (node (ref "U1") (pin "1") (pinfunction "NC_1") (pintype "bidirectional"))
    )
    (net (code "88") (name "unconnected-(U1-NC-Pad24)") (class "Default")
      (node (ref "U1") (pin "24") (pinfunction "NC_24") (pintype "bidirectional"))
    )
    (net (code "89") (name "unconnected-(U1-NC-Pad30)") (class "Default")
      (node (ref "U1") (pin "30") (pinfunction "NC_30") (pintype "bidirectional"))
    )
  )
)
